# 1_Main_copy.net
KiCad netlist of a schematic drawn in Altium Designer
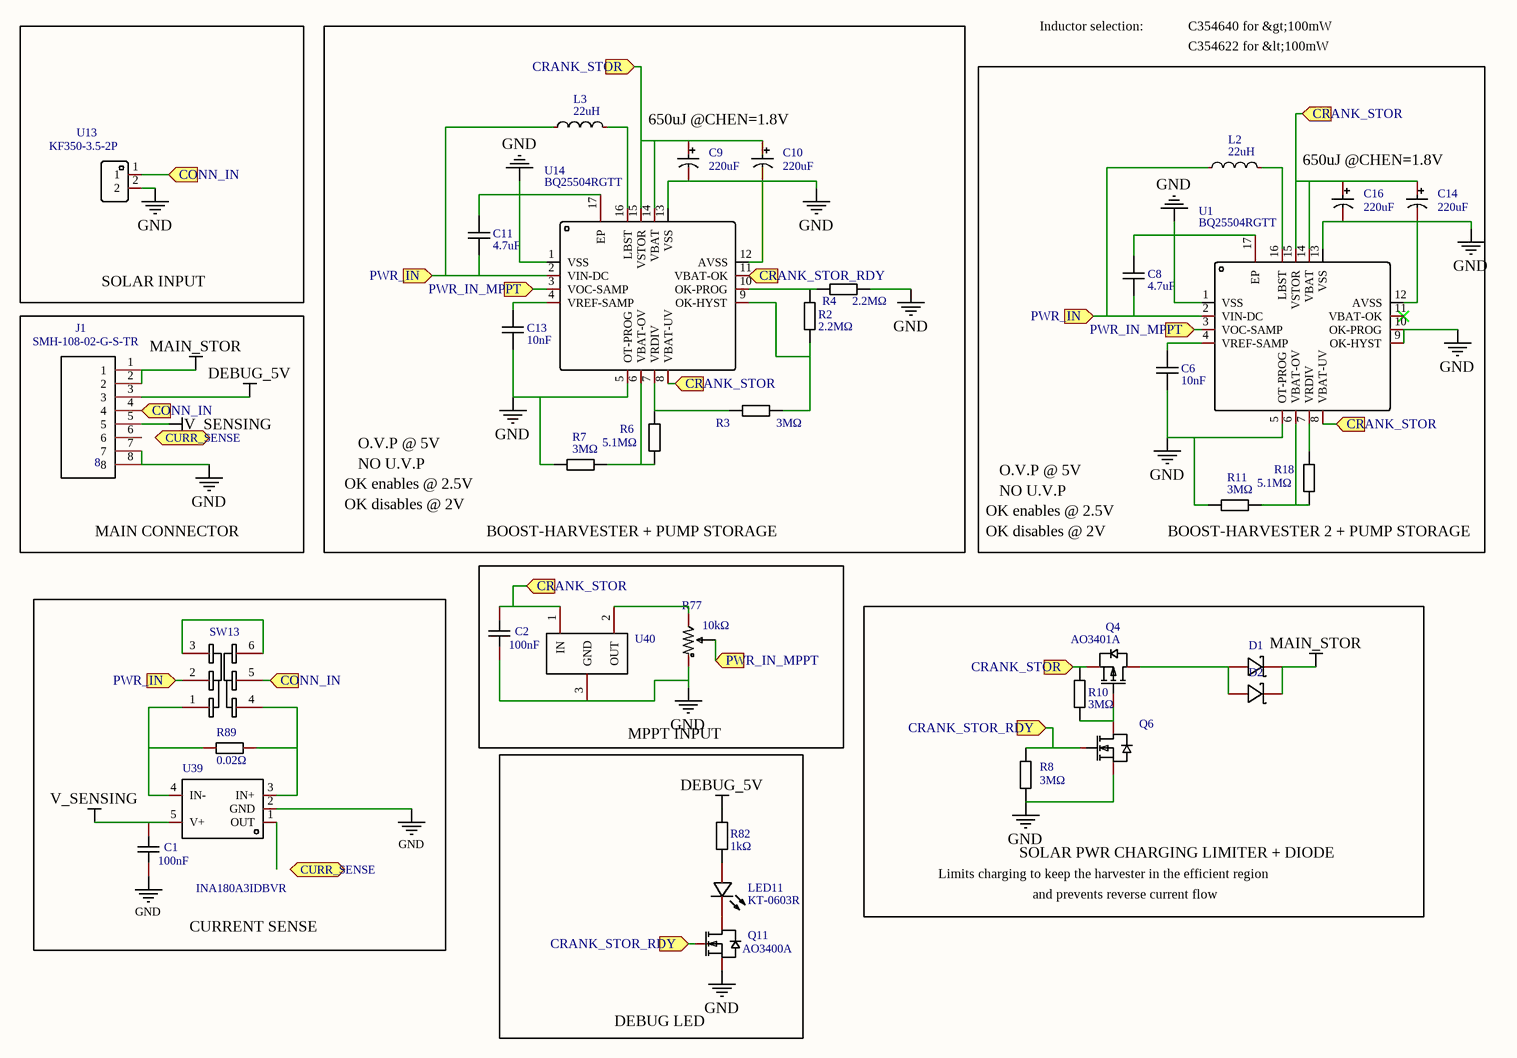
[diagram p0: 1_Main copy.schdoc]

(export (version "E")
  (design (tool "Eeschema 10.0.6"))
  (components
    (comp (ref "C1")
      (value "100nF")
      (fields
        (field (name "NAME") "100nF")
        (field (name "MANUFACTURER") "YAGEO")
        (field (name "MANUFACTURER PART") "CC0603KRX7R9BB104")
      )
      (libsource (lib "altium-import") (part "root_1_CC0603KRX7R9BB104_"))
    )
    (comp (ref "C2")
      (value "100nF")
      (fields
        (field (name "NAME") "100nF")
        (field (name "MANUFACTURER") "YAGEO")
        (field (name "MANUFACTURER PART") "CC0603KRX7R9BB104")
      )
      (libsource (lib "altium-import") (part "root_1_CC0603KRX7R9BB104_"))
    )
    (comp (ref "C6")
      (value "10nF")
      (fields
        (field (name "NAME") "10nF")
        (field (name "MANUFACTURER") "FH")
        (field (name "MANUFACTURER PART") "0603B103K500NT")
      )
      (libsource (lib "altium-import") (part "root_1_0603B103K500NT_"))
    )
    (comp (ref "C8")
      (value "4.7uF")
      (fields
        (field (name "NAME") "4.7uF")
        (field (name "MANUFACTURER PART") "CL10A475KO8NNNC")
        (field (name "MANUFACTURER") "SAMSUNG")
      )
      (libsource (lib "altium-import") (part "root_1_CL10A475KO8NNNC_"))
    )
    (comp (ref "C9")
      (value "220uF")
      (fields
        (field (name "NAME") "220uF")
        (field (name "MANUFACTURER") "HONOR")
        (field (name "MANUFACTURER PART") "RVT1A221M0605")
      )
      (libsource (lib "altium-import") (part "root_0_RVT1A221M0605_"))
    )
    (comp (ref "C10")
      (value "220uF")
      (fields
        (field (name "NAME") "220uF")
        (field (name "MANUFACTURER") "HONOR")
        (field (name "MANUFACTURER PART") "RVT1A221M0605")
      )
      (libsource (lib "altium-import") (part "root_0_RVT1A221M0605_"))
    )
    (comp (ref "C11")
      (value "4.7uF")
      (fields
        (field (name "NAME") "4.7uF")
        (field (name "MANUFACTURER PART") "CL10A475KO8NNNC")
        (field (name "MANUFACTURER") "SAMSUNG")
      )
      (libsource (lib "altium-import") (part "root_1_CL10A475KO8NNNC_"))
    )
    (comp (ref "C13")
      (value "10nF")
      (fields
        (field (name "NAME") "10nF")
        (field (name "MANUFACTURER") "FH")
        (field (name "MANUFACTURER PART") "0603B103K500NT")
      )
      (libsource (lib "altium-import") (part "root_1_0603B103K500NT_"))
    )
    (comp (ref "C14")
      (value "220uF")
      (fields
        (field (name "NAME") "220uF")
        (field (name "MANUFACTURER") "HONOR")
        (field (name "MANUFACTURER PART") "RVT1A221M0605")
      )
      (libsource (lib "altium-import") (part "root_0_RVT1A221M0605_"))
    )
    (comp (ref "C16")
      (value "220uF")
      (fields
        (field (name "NAME") "220uF")
        (field (name "MANUFACTURER") "HONOR")
        (field (name "MANUFACTURER PART") "RVT1A221M0605")
      )
      (libsource (lib "altium-import") (part "root_0_RVT1A221M0605_"))
    )
    (comp (ref "D1")
      (value "SS54")
      (description "Reverse Voltage (Vr):40V Average Rectified Current (Io):5A Forward Voltage (Vf@If):550mV@5A")
      (fields (field (name "MANUFACTURER") "MDD"))
      (libsource (lib "altium-import") (part "root_2_SS54_"))
    )
    (comp (ref "D2")
      (value "SS54")
      (description "Reverse Voltage (Vr):40V Average Rectified Current (Io):5A Forward Voltage (Vf@If):550mV@5A")
      (fields (field (name "MANUFACTURER") "MDD"))
      (libsource (lib "altium-import") (part "root_2_SS54_"))
    )
    (comp (ref "J1")
      (value "SMH-108-02-G-S-TR")
      (fields (field (name "NAME") "SMH-108-02-G-S-TR") (field (name "NAME_1") "8"))
      (libsource (lib "altium-import") (part "root_0_SMH-108-02-G-S-TR_"))
    )
    (comp (ref "L2")
      (value "22uH")
      (fields
        (field (name "NAME") "22uH")
        (field (name "MANUFACTURER") "CENKER")
        (field (name "MANUFACTURER PART") "CKCS6028-22uH/M")
      )
      (libsource (lib "altium-import") (part "root_0_CKCS6028-22uH/M_"))
    )
    (comp (ref "L3")
      (value "22uH")
      (fields
        (field (name "NAME") "22uH")
        (field (name "MANUFACTURER") "CENKER")
        (field (name "MANUFACTURER PART") "CKCS6028-22uH/M")
      )
      (libsource (lib "altium-import") (part "root_0_CKCS6028-22uH/M_"))
    )
    (comp (ref "LED11")
      (value "KT-0603R")
      (fields (field (name "NAME") "KT-0603R") (field (name "MANUFACTURER") "KENTO"))
      (libsource (lib "altium-import") (part "root_1_KT-0603R_"))
    )
    (comp (ref "Q4")
      (value "AO3401A")
      (fields (field (name "NAME") "AO3401A") (field (name "MANUFACTURER") "AOS"))
      (libsource (lib "altium-import") (part "root_1_AO3401A_"))
    )
    (comp (ref "Q6")
      (value "SI2302")
      (fields (field (name "MANUFACTURER") "YONGYUTAI(永裕泰)"))
      (libsource (lib "altium-import") (part "root_0_SI2302_"))
    )
    (comp (ref "Q11")
      (value "AO3400A")
      (fields (field (name "NAME") "AO3400A") (field (name "MANUFACTURER") "HUASHUO(华朔)"))
      (libsource (lib "altium-import") (part "root_0_AO3400A_"))
    )
    (comp (ref "R2")
      (value "2.2MΩ")
      (fields
        (field (name "NAME") "2.2MΩ")
        (field (name "MANUFACTURER") "UniOhm")
        (field (name "MANUFACTURER PART") "0603WAF2204T5E")
      )
      (libsource (lib "altium-import") (part "root_1_0603WAF2204T5E_"))
    )
    (comp (ref "R3")
      (value "3MΩ")
      (fields
        (field (name "NAME") "3MΩ")
        (field (name "MANUFACTURER") "UniOhm")
        (field (name "MANUFACTURER PART") "0603WAF3004T5E")
      )
      (libsource (lib "altium-import") (part "root_2_0603WAF3004T5E_"))
    )
    (comp (ref "R4")
      (value "2.2MΩ")
      (fields
        (field (name "NAME") "2.2MΩ")
        (field (name "MANUFACTURER") "UniOhm")
        (field (name "MANUFACTURER PART") "0603WAF2204T5E")
      )
      (libsource (lib "altium-import") (part "root_0_0603WAF2204T5E_"))
    )
    (comp (ref "R6")
      (value "5.1MΩ")
      (fields
        (field (name "NAME") "5.1MΩ")
        (field (name "MANUFACTURER") "UniOhm")
        (field (name "MANUFACTURER PART") "0603WAF5104T5E")
      )
      (libsource (lib "altium-import") (part "root_1_0603WAF5104T5E_"))
    )
    (comp (ref "R7")
      (value "3MΩ")
      (fields
        (field (name "NAME") "3MΩ")
        (field (name "MANUFACTURER") "UniOhm")
        (field (name "MANUFACTURER PART") "0603WAF3004T5E")
      )
      (libsource (lib "altium-import") (part "root_0_0603WAF3004T5E_"))
    )
    (comp (ref "R8")
      (value "3MΩ")
      (fields
        (field (name "NAME") "3MΩ")
        (field (name "MANUFACTURER") "UniOhm")
        (field (name "MANUFACTURER PART") "0603WAF3004T5E")
      )
      (libsource (lib "altium-import") (part "root_3_0603WAF3004T5E_"))
    )
    (comp (ref "R10")
      (value "3MΩ")
      (fields
        (field (name "NAME") "3MΩ")
        (field (name "MANUFACTURER") "UniOhm")
        (field (name "MANUFACTURER PART") "0603WAF3004T5E")
      )
      (libsource (lib "altium-import") (part "root_1_0603WAF3004T5E_"))
    )
    (comp (ref "R11")
      (value "3MΩ")
      (fields
        (field (name "NAME") "3MΩ")
        (field (name "MANUFACTURER") "UniOhm")
        (field (name "MANUFACTURER PART") "0603WAF3004T5E")
      )
      (libsource (lib "altium-import") (part "root_0_0603WAF3004T5E_"))
    )
    (comp (ref "R18")
      (value "5.1MΩ")
      (fields
        (field (name "NAME") "5.1MΩ")
        (field (name "MANUFACTURER") "UniOhm")
        (field (name "MANUFACTURER PART") "0603WAF5104T5E")
      )
      (libsource (lib "altium-import") (part "root_1_0603WAF5104T5E_"))
    )
    (comp (ref "R77")
      (value "10kΩ")
      (description "Resistance:10kΩ Tolerance:±10% Temperature Coefficient:±250ppm/ Temperature Coefficient:±250ppm/")
      (fields (field (name "MANUFACTURER") "BOCHEN(博晨)") (field (name "MANUFACTURER PART") "3362P-1-103"))
      (libsource (lib "altium-import") (part "root_3_3362P-1-103_"))
    )
    (comp (ref "R82")
      (value "1kΩ")
      (fields
        (field (name "NAME") "1kΩ")
        (field (name "MANUFACTURER") "UniOhm")
        (field (name "MANUFACTURER PART") "0603WAF1001T5E")
      )
      (libsource (lib "altium-import") (part "root_1_0603WAF1001T5E_"))
    )
    (comp (ref "R89")
      (value "0.02Ω")
      (fields
        (field (name "MANUFACTURER") "YAGEO(国巨)")
        (field (name "MANUFACTURER PART") "RL0805FR-070R02L")
        (field (name "TOLERANCE") "±1%")
      )
      (libsource (lib "altium-import") (part "root_0_RL0805FR-070R02L_"))
    )
    (comp (ref "SW13")
      (value "K3-2235D-F1")
      (fields (field (name "MANUFACTURER") "韩国韩荣"))
      (libsource (lib "altium-import") (part "root_1_K3-2235D-F1_"))
    )
    (comp (ref "U1")
      (value "BQ25504RGTT")
      (fields (field (name "NAME") "BQ25504RGTT") (field (name "MANUFACTURER") "Texas Instruments"))
      (libsource (lib "altium-import") (part "root_0_BQ25504RGTT_"))
    )
    (comp (ref "U13")
      (value "KF350-3.5-2P")
      (fields (field (name "NAME") "KF350-3.5-2P") (field (name "MANUFACTURER") "Cixi Kefa Elec"))
      (libsource (lib "altium-import") (part "root_2_KF350-3.5-2P_"))
    )
    (comp (ref "U14")
      (value "BQ25504RGTT")
      (fields (field (name "NAME") "BQ25504RGTT") (field (name "MANUFACTURER") "Texas Instruments"))
      (libsource (lib "altium-import") (part "root_0_BQ25504RGTT_"))
    )
    (comp (ref "U39")
      (value "INA180A3IDBVR")
      (fields (field (name "LCSC PART NAME") "INA180A3IDBVR") (field (name "MANUFACTURER") "TI(德州仪器)"))
      (libsource (lib "altium-import") (part "root_2_INA180A3IDBVR_"))
    )
    (comp (ref "U40")
      (value "REF3318AIDBZT")
      (fields (field (name "MANUFACTURER") "TI(德州仪器)") (field (name "TOLERANCE") "±0.15%"))
      (libsource (lib "altium-import") (part "root_2_mirrored_REF3318AIDBZT_"))
    )
  )
  (nets
    (net (code "1") (name "/CONN_IN") (class "Default")
      (node (ref "J1") (pin "4") (pinfunction "4_4") (pintype "passive"))
      (node (ref "SW13") (pin "5") (pinfunction "5_5") (pintype "passive"))
      (node (ref "U13") (pin "1") (pinfunction "1_1") (pintype "passive"))
    )
    (net (code "2") (name "/CRANK_STOR") (class "Default")
      (node (ref "C10") (pin "1") (pinfunction "1_1") (pintype "passive"))
      (node (ref "C14") (pin "1") (pinfunction "1_1") (pintype "passive"))
      (node (ref "C16") (pin "1") (pinfunction "1_1") (pintype "passive"))
      (node (ref "C2") (pin "2") (pinfunction "2_2") (pintype "passive"))
      (node (ref "C9") (pin "1") (pinfunction "1_1") (pintype "passive"))
      (node (ref "Q4") (pin "2") (pinfunction "S_2") (pintype "passive"))
      (node (ref "R10") (pin "2") (pinfunction "2_2") (pintype "passive"))
      (node (ref "U1") (pin "14") (pinfunction "VBAT_14") (pintype "passive"))
      (node (ref "U1") (pin "15") (pinfunction "VSTOR_15") (pintype "passive"))
      (node (ref "U1") (pin "8") (pinfunction "VBAT-UV_8") (pintype "passive"))
      (node (ref "U14") (pin "14") (pinfunction "VBAT_14") (pintype "passive"))
      (node (ref "U14") (pin "15") (pinfunction "VSTOR_15") (pintype "passive"))
      (node (ref "U14") (pin "8") (pinfunction "VBAT-UV_8") (pintype "passive"))
      (node (ref "U40") (pin "1") (pinfunction "IN_1") (pintype "passive"))
    )
    (net (code "3") (name "/CRANK_STOR_RDY") (class "Default")
      (node (ref "Q11") (pin "1") (pinfunction "G_1") (pintype "passive"))
      (node (ref "Q6") (pin "1") (pinfunction "G_1") (pintype "passive"))
      (node (ref "R8") (pin "1") (pinfunction "1_1") (pintype "passive"))
      (node (ref "U14") (pin "11") (pinfunction "VBAT-OK_11") (pintype "passive"))
    )
    (net (code "5") (name "/PWR_IN") (class "Default")
      (node (ref "C11") (pin "1") (pinfunction "1_1") (pintype "passive"))
      (node (ref "C8") (pin "1") (pinfunction "1_1") (pintype "passive"))
      (node (ref "L2") (pin "1") (pinfunction "1_1") (pintype "passive"))
      (node (ref "L3") (pin "1") (pinfunction "1_1") (pintype "passive"))
      (node (ref "SW13") (pin "2") (pinfunction "2_2") (pintype "passive"))
      (node (ref "U1") (pin "2") (pinfunction "VIN-DC_2") (pintype "passive"))
      (node (ref "U14") (pin "2") (pinfunction "VIN-DC_2") (pintype "passive"))
    )
    (net (code "6") (name "/PWR_IN_MPPT") (class "Default")
      (node (ref "R77") (pin "2") (pinfunction "2_2") (pintype "passive"))
      (node (ref "U1") (pin "3") (pinfunction "VOC-SAMP_3") (pintype "passive"))
      (node (ref "U14") (pin "3") (pinfunction "VOC-SAMP_3") (pintype "passive"))
    )
    (net (code "7") (name "DEBUG_5V") (class "Default")
      (node (ref "J1") (pin "3") (pinfunction "3_3") (pintype "passive"))
      (node (ref "R82") (pin "2") (pinfunction "2_2") (pintype "passive"))
    )
    (net (code "8") (name "GND") (class "Default")
      (node (ref "C1") (pin "1") (pinfunction "1_1") (pintype "passive"))
      (node (ref "C10") (pin "2") (pinfunction "2_2") (pintype "passive"))
      (node (ref "C11") (pin "2") (pinfunction "2_2") (pintype "passive"))
      (node (ref "C13") (pin "1") (pinfunction "1_1") (pintype "passive"))
      (node (ref "C14") (pin "2") (pinfunction "2_2") (pintype "passive"))
      (node (ref "C16") (pin "2") (pinfunction "2_2") (pintype "passive"))
      (node (ref "C2") (pin "1") (pinfunction "1_1") (pintype "passive"))
      (node (ref "C6") (pin "1") (pinfunction "1_1") (pintype "passive"))
      (node (ref "C8") (pin "2") (pinfunction "2_2") (pintype "passive"))
      (node (ref "C9") (pin "2") (pinfunction "2_2") (pintype "passive"))
      (node (ref "J1") (pin "7") (pinfunction "7_7") (pintype "passive"))
      (node (ref "J1") (pin "8") (pinfunction "8_8") (pintype "passive"))
      (node (ref "Q11") (pin "2") (pinfunction "S_2") (pintype "passive"))
      (node (ref "Q6") (pin "2") (pinfunction "S_2") (pintype "passive"))
      (node (ref "R11") (pin "1") (pinfunction "1_1") (pintype "passive"))
      (node (ref "R4") (pin "2") (pinfunction "2_2") (pintype "passive"))
      (node (ref "R7") (pin "1") (pinfunction "1_1") (pintype "passive"))
      (node (ref "R77") (pin "1") (pinfunction "1_1") (pintype "passive"))
      (node (ref "R8") (pin "2") (pinfunction "2_2") (pintype "passive"))
      (node (ref "U1") (pin "1") (pinfunction "VSS_1") (pintype "passive"))
      (node (ref "U1") (pin "10") (pinfunction "OK-PROG_10") (pintype "passive"))
      (node (ref "U1") (pin "12") (pinfunction "AVSS_12") (pintype "passive"))
      (node (ref "U1") (pin "13") (pinfunction "VSS_13") (pintype "passive"))
      (node (ref "U1") (pin "17") (pinfunction "EP_17") (pintype "passive"))
      (node (ref "U1") (pin "5") (pinfunction "OT-PROG_5") (pintype "passive"))
      (node (ref "U1") (pin "9") (pinfunction "OK-HYST_9") (pintype "passive"))
      (node (ref "U13") (pin "2") (pinfunction "2_2") (pintype "passive"))
      (node (ref "U14") (pin "1") (pinfunction "VSS_1") (pintype "passive"))
      (node (ref "U14") (pin "12") (pinfunction "AVSS_12") (pintype "passive"))
      (node (ref "U14") (pin "13") (pinfunction "VSS_13") (pintype "passive"))
      (node (ref "U14") (pin "17") (pinfunction "EP_17") (pintype "passive"))
      (node (ref "U14") (pin "5") (pinfunction "OT-PROG_5") (pintype "passive"))
      (node (ref "U39") (pin "2") (pinfunction "GND_2") (pintype "passive"))
      (node (ref "U40") (pin "3") (pinfunction "GND_3") (pintype "passive"))
    )
    (net (code "9") (name "MAIN_STOR") (class "Default")
      (node (ref "D1") (pin "2") (pinfunction "K_2") (pintype "passive"))
      (node (ref "D2") (pin "2") (pinfunction "K_2") (pintype "passive"))
      (node (ref "J1") (pin "1") (pinfunction "1_1") (pintype "passive"))
      (node (ref "J1") (pin "2") (pinfunction "2_2") (pintype "passive"))
    )
    (net (code "10") (name "Net-(D1-A)") (class "Default")
      (node (ref "D1") (pin "1") (pinfunction "A_1") (pintype "passive"))
      (node (ref "D2") (pin "1") (pinfunction "A_1") (pintype "passive"))
      (node (ref "Q4") (pin "3") (pinfunction "D_3") (pintype "passive"))
    )
    (net (code "11") (name "Net-(LED11-A)") (class "Default")
      (node (ref "LED11") (pin "1") (pinfunction "A_1") (pintype "passive"))
      (node (ref "R82") (pin "1") (pinfunction "1_1") (pintype "passive"))
    )
    (net (code "12") (name "Net-(LED11-K)") (class "Default")
      (node (ref "LED11") (pin "2") (pinfunction "K_2") (pintype "passive"))
      (node (ref "Q11") (pin "3") (pinfunction "D_3") (pintype "passive"))
    )
    (net (code "13") (name "Net-(Q4-G)") (class "Default")
      (node (ref "Q4") (pin "1") (pinfunction "G_1") (pintype "passive"))
      (node (ref "Q6") (pin "3") (pinfunction "D_3") (pintype "passive"))
      (node (ref "R10") (pin "1") (pinfunction "1_1") (pintype "passive"))
    )
    (net (code "14") (name "Net-(SW13-Pad3)") (class "Default")
      (node (ref "SW13") (pin "3") (pinfunction "3_3") (pintype "passive"))
      (node (ref "SW13") (pin "6") (pinfunction "6_6") (pintype "passive"))
    )
    (net (code "15") (name "Net-(U1-LBST)") (class "Default")
      (node (ref "L2") (pin "2") (pinfunction "2_2") (pintype "passive"))
      (node (ref "U1") (pin "16") (pinfunction "LBST_16") (pintype "passive"))
    )
    (net (code "16") (name "Net-(U1-VBAT-OV)") (class "Default")
      (node (ref "R11") (pin "2") (pinfunction "2_2") (pintype "passive"))
      (node (ref "R18") (pin "2") (pinfunction "2_2") (pintype "passive"))
      (node (ref "U1") (pin "6") (pinfunction "VBAT-OV_6") (pintype "passive"))
    )
    (net (code "17") (name "Net-(U1-VRDIV)") (class "Default")
      (node (ref "R18") (pin "1") (pinfunction "1_1") (pintype "passive"))
      (node (ref "U1") (pin "7") (pinfunction "VRDIV_7") (pintype "passive"))
    )
    (net (code "18") (name "Net-(U1-VREF-SAMP)") (class "Default")
      (node (ref "C6") (pin "2") (pinfunction "2_2") (pintype "passive"))
      (node (ref "U1") (pin "4") (pinfunction "VREF-SAMP_4") (pintype "passive"))
    )
    (net (code "19") (name "Net-(U14-LBST)") (class "Default")
      (node (ref "L3") (pin "2") (pinfunction "2_2") (pintype "passive"))
      (node (ref "U14") (pin "16") (pinfunction "LBST_16") (pintype "passive"))
    )
    (net (code "20") (name "Net-(U14-OK-HYST)") (class "Default")
      (node (ref "R2") (pin "1") (pinfunction "1_1") (pintype "passive"))
      (node (ref "R3") (pin "1") (pinfunction "1_1") (pintype "passive"))
      (node (ref "U14") (pin "9") (pinfunction "OK-HYST_9") (pintype "passive"))
    )
    (net (code "21") (name "Net-(U14-OK-PROG)") (class "Default")
      (node (ref "R2") (pin "2") (pinfunction "2_2") (pintype "passive"))
      (node (ref "R4") (pin "1") (pinfunction "1_1") (pintype "passive"))
      (node (ref "U14") (pin "10") (pinfunction "OK-PROG_10") (pintype "passive"))
    )
    (net (code "22") (name "Net-(U14-VBAT-OV)") (class "Default")
      (node (ref "R6") (pin "2") (pinfunction "2_2") (pintype "passive"))
      (node (ref "R7") (pin "2") (pinfunction "2_2") (pintype "passive"))
      (node (ref "U14") (pin "6") (pinfunction "VBAT-OV_6") (pintype "passive"))
    )
    (net (code "23") (name "Net-(U14-VRDIV)") (class "Default")
      (node (ref "R3") (pin "2") (pinfunction "2_2") (pintype "passive"))
      (node (ref "R6") (pin "1") (pinfunction "1_1") (pintype "passive"))
      (node (ref "U14") (pin "7") (pinfunction "VRDIV_7") (pintype "passive"))
    )
    (net (code "24") (name "Net-(U14-VREF-SAMP)") (class "Default")
      (node (ref "C13") (pin "2") (pinfunction "2_2") (pintype "passive"))
      (node (ref "U14") (pin "4") (pinfunction "VREF-SAMP_4") (pintype "passive"))
    )
    (net (code "25") (name "Net-(U39-IN+)") (class "Default")
      (node (ref "R89") (pin "2") (pinfunction "2_2") (pintype "passive"))
      (node (ref "SW13") (pin "4") (pinfunction "4_4") (pintype "passive"))
      (node (ref "U39") (pin "3") (pinfunction "IN+_3") (pintype "passive"))
    )
    (net (code "26") (name "Net-(U39-IN-)") (class "Default")
      (node (ref "R89") (pin "1") (pinfunction "1_1") (pintype "passive"))
      (node (ref "SW13") (pin "1") (pinfunction "1_1") (pintype "passive"))
      (node (ref "U39") (pin "4") (pinfunction "IN-_4") (pintype "passive"))
    )
    (net (code "27") (name "Net-(U40-OUT)") (class "Default")
      (node (ref "R77") (pin "3") (pinfunction "3_3") (pintype "passive"))
      (node (ref "U40") (pin "2") (pinfunction "OUT_2") (pintype "passive"))
    )
    (net (code "28") (name "V_SENSING") (class "Default")
      (node (ref "C1") (pin "2") (pinfunction "2_2") (pintype "passive"))
      (node (ref "J1") (pin "5") (pinfunction "5_5") (pintype "passive"))
      (node (ref "U39") (pin "5") (pinfunction "V+_5") (pintype "passive"))
    )
    (net (code "29") (name "unconnected-(J1-Pad6)") (class "Default")
      (node (ref "J1") (pin "6") (pinfunction "6_6") (pintype "passive"))
    )
    (net (code "30") (name "unconnected-(U1-VBAT-OK-Pad11)") (class "Default")
      (node (ref "U1") (pin "11") (pinfunction "VBAT-OK_11") (pintype "passive+no_connect"))
    )
    (net (code "31") (name "unconnected-(U39-OUT-Pad1)") (class "Default")
      (node (ref "U39") (pin "1") (pinfunction "OUT_1") (pintype "passive"))
    )
  )
)
